# SmartChessMultiplex_SCH.net
KiCad netlist of a schematic drawn in Altium Designer
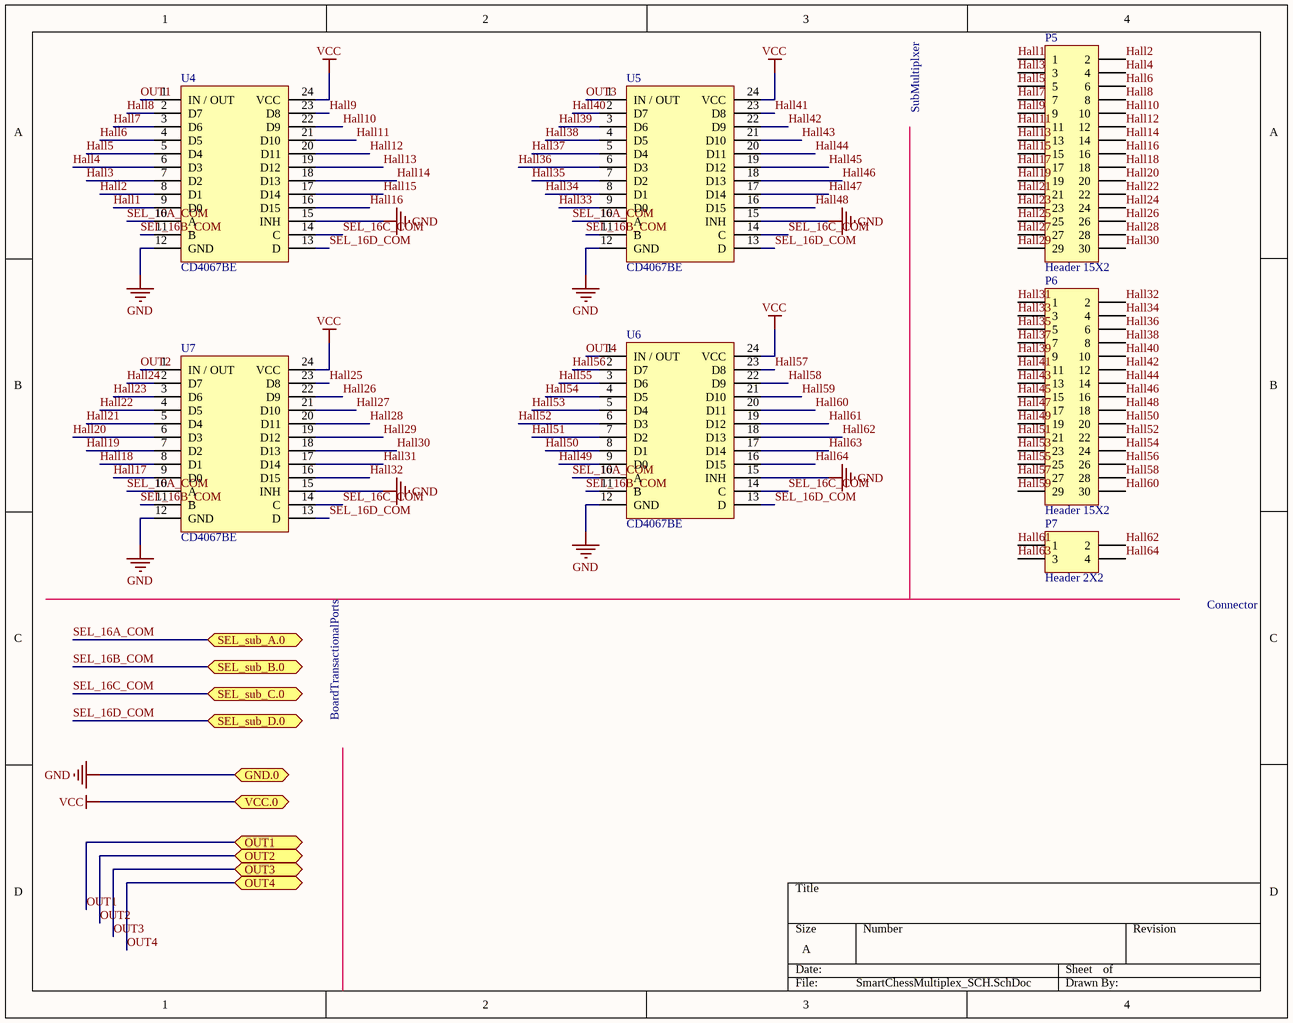
[diagram p0: SmartChessMultiplex_SCH.SchDoc]

(export (version "E")
  (design (tool "Eeschema 10.0.6"))
  (components
    (comp (ref "P5")
      (value "Header 15X2")
      (footprint "HDR2X15")
      (description "Header, 15-Pin, Dual row")
      (fields (field (name "PUBLISHER") "Altium Limited"))
      (libsource (lib "Miscellaneous Connectors") (part "Header 15X2"))
    )
    (comp (ref "P6")
      (value "Header 15X2")
      (footprint "HDR2X15")
      (description "Header, 15-Pin, Dual row")
      (fields (field (name "PUBLISHER") "Altium Limited"))
      (libsource (lib "Miscellaneous Connectors") (part "Header 15X2"))
    )
    (comp (ref "P7")
      (value "Header 2X2")
      (footprint "HDR2X2")
      (description "Header, 2-Pin, Dual row")
      (fields (field (name "PUBLISHER") "Altium Limited"))
      (libsource (lib "Miscellaneous Connectors") (part "Header 2X2"))
    )
    (comp (ref "U4") (value "CD4067BE") (footprint "DIP24") (libsource (lib "My_lib_new") (part "CD4067BE")))
    (comp (ref "U5") (value "CD4067BE") (footprint "DIP24") (libsource (lib "My_lib_new") (part "CD4067BE")))
    (comp (ref "U6") (value "CD4067BE") (footprint "DIP24") (libsource (lib "My_lib_new") (part "CD4067BE")))
    (comp (ref "U7") (value "CD4067BE") (footprint "DIP24") (libsource (lib "My_lib_new") (part "CD4067BE")))
  )
  (nets
    (net (code "1") (name "/Hall1") (class "Default")
      (node (ref "P5") (pin "1") (pinfunction "1_1") (pintype "passive"))
      (node (ref "U4") (pin "9") (pinfunction "D0_9") (pintype "passive"))
    )
    (net (code "2") (name "/Hall2") (class "Default")
      (node (ref "P5") (pin "2") (pinfunction "2_2") (pintype "passive"))
      (node (ref "U4") (pin "8") (pinfunction "D1_8") (pintype "passive"))
    )
    (net (code "3") (name "/Hall3") (class "Default")
      (node (ref "P5") (pin "3") (pinfunction "3_3") (pintype "passive"))
      (node (ref "U4") (pin "7") (pinfunction "D2_7") (pintype "passive"))
    )
    (net (code "4") (name "/Hall4") (class "Default")
      (node (ref "P5") (pin "4") (pinfunction "4_4") (pintype "passive"))
      (node (ref "U4") (pin "6") (pinfunction "D3_6") (pintype "passive"))
    )
    (net (code "5") (name "/Hall5") (class "Default")
      (node (ref "P5") (pin "5") (pinfunction "5_5") (pintype "passive"))
      (node (ref "U4") (pin "5") (pinfunction "D4_5") (pintype "passive"))
    )
    (net (code "6") (name "/Hall6") (class "Default")
      (node (ref "P5") (pin "6") (pinfunction "6_6") (pintype "passive"))
      (node (ref "U4") (pin "4") (pinfunction "D5_4") (pintype "passive"))
    )
    (net (code "7") (name "/Hall7") (class "Default")
      (node (ref "P5") (pin "7") (pinfunction "7_7") (pintype "passive"))
      (node (ref "U4") (pin "3") (pinfunction "D6_3") (pintype "passive"))
    )
    (net (code "8") (name "/Hall8") (class "Default")
      (node (ref "P5") (pin "8") (pinfunction "8_8") (pintype "passive"))
      (node (ref "U4") (pin "2") (pinfunction "D7_2") (pintype "passive"))
    )
    (net (code "9") (name "/Hall9") (class "Default")
      (node (ref "P5") (pin "9") (pinfunction "9_9") (pintype "passive"))
      (node (ref "U4") (pin "23") (pinfunction "D8_23") (pintype "passive"))
    )
    (net (code "10") (name "/Hall10") (class "Default")
      (node (ref "P5") (pin "10") (pinfunction "10_10") (pintype "passive"))
      (node (ref "U4") (pin "22") (pinfunction "D9_22") (pintype "passive"))
    )
    (net (code "11") (name "/Hall11") (class "Default")
      (node (ref "P5") (pin "11") (pinfunction "11_11") (pintype "passive"))
      (node (ref "U4") (pin "21") (pinfunction "D10_21") (pintype "passive"))
    )
    (net (code "12") (name "/Hall12") (class "Default")
      (node (ref "P5") (pin "12") (pinfunction "12_12") (pintype "passive"))
      (node (ref "U4") (pin "20") (pinfunction "D11_20") (pintype "passive"))
    )
    (net (code "13") (name "/Hall13") (class "Default")
      (node (ref "P5") (pin "13") (pinfunction "13_13") (pintype "passive"))
      (node (ref "U4") (pin "19") (pinfunction "D12_19") (pintype "passive"))
    )
    (net (code "14") (name "/Hall14") (class "Default")
      (node (ref "P5") (pin "14") (pinfunction "14_14") (pintype "passive"))
      (node (ref "U4") (pin "18") (pinfunction "D13_18") (pintype "passive"))
    )
    (net (code "15") (name "/Hall15") (class "Default")
      (node (ref "P5") (pin "15") (pinfunction "15_15") (pintype "passive"))
      (node (ref "U4") (pin "17") (pinfunction "D14_17") (pintype "passive"))
    )
    (net (code "16") (name "/Hall16") (class "Default")
      (node (ref "P5") (pin "16") (pinfunction "16_16") (pintype "passive"))
      (node (ref "U4") (pin "16") (pinfunction "D15_16") (pintype "passive"))
    )
    (net (code "17") (name "/Hall17") (class "Default")
      (node (ref "P5") (pin "17") (pinfunction "17_17") (pintype "passive"))
      (node (ref "U7") (pin "9") (pinfunction "D0_9") (pintype "passive"))
    )
    (net (code "18") (name "/Hall18") (class "Default")
      (node (ref "P5") (pin "18") (pinfunction "18_18") (pintype "passive"))
      (node (ref "U7") (pin "8") (pinfunction "D1_8") (pintype "passive"))
    )
    (net (code "19") (name "/Hall19") (class "Default")
      (node (ref "P5") (pin "19") (pinfunction "19_19") (pintype "passive"))
      (node (ref "U7") (pin "7") (pinfunction "D2_7") (pintype "passive"))
    )
    (net (code "20") (name "/Hall20") (class "Default")
      (node (ref "P5") (pin "20") (pinfunction "20_20") (pintype "passive"))
      (node (ref "U7") (pin "6") (pinfunction "D3_6") (pintype "passive"))
    )
    (net (code "21") (name "/Hall21") (class "Default")
      (node (ref "P5") (pin "21") (pinfunction "21_21") (pintype "passive"))
      (node (ref "U7") (pin "5") (pinfunction "D4_5") (pintype "passive"))
    )
    (net (code "22") (name "/Hall22") (class "Default")
      (node (ref "P5") (pin "22") (pinfunction "22_22") (pintype "passive"))
      (node (ref "U7") (pin "4") (pinfunction "D5_4") (pintype "passive"))
    )
    (net (code "23") (name "/Hall23") (class "Default")
      (node (ref "P5") (pin "23") (pinfunction "23_23") (pintype "passive"))
      (node (ref "U7") (pin "3") (pinfunction "D6_3") (pintype "passive"))
    )
    (net (code "24") (name "/Hall24") (class "Default")
      (node (ref "P5") (pin "24") (pinfunction "24_24") (pintype "passive"))
      (node (ref "U7") (pin "2") (pinfunction "D7_2") (pintype "passive"))
    )
    (net (code "25") (name "/Hall25") (class "Default")
      (node (ref "P5") (pin "25") (pinfunction "25_25") (pintype "passive"))
      (node (ref "U7") (pin "23") (pinfunction "D8_23") (pintype "passive"))
    )
    (net (code "26") (name "/Hall26") (class "Default")
      (node (ref "P5") (pin "26") (pinfunction "26_26") (pintype "passive"))
      (node (ref "U7") (pin "22") (pinfunction "D9_22") (pintype "passive"))
    )
    (net (code "27") (name "/Hall27") (class "Default")
      (node (ref "P5") (pin "27") (pinfunction "27_27") (pintype "passive"))
      (node (ref "U7") (pin "21") (pinfunction "D10_21") (pintype "passive"))
    )
    (net (code "28") (name "/Hall28") (class "Default")
      (node (ref "P5") (pin "28") (pinfunction "28_28") (pintype "passive"))
      (node (ref "U7") (pin "20") (pinfunction "D11_20") (pintype "passive"))
    )
    (net (code "29") (name "/Hall29") (class "Default")
      (node (ref "P5") (pin "29") (pinfunction "29_29") (pintype "passive"))
      (node (ref "U7") (pin "19") (pinfunction "D12_19") (pintype "passive"))
    )
    (net (code "30") (name "/Hall30") (class "Default")
      (node (ref "P5") (pin "30") (pinfunction "30_30") (pintype "passive"))
      (node (ref "U7") (pin "18") (pinfunction "D13_18") (pintype "passive"))
    )
    (net (code "31") (name "/Hall31") (class "Default")
      (node (ref "P6") (pin "1") (pinfunction "1_1") (pintype "passive"))
      (node (ref "U7") (pin "17") (pinfunction "D14_17") (pintype "passive"))
    )
    (net (code "32") (name "/Hall32") (class "Default")
      (node (ref "P6") (pin "2") (pinfunction "2_2") (pintype "passive"))
      (node (ref "U7") (pin "16") (pinfunction "D15_16") (pintype "passive"))
    )
    (net (code "33") (name "/Hall33") (class "Default")
      (node (ref "P6") (pin "3") (pinfunction "3_3") (pintype "passive"))
      (node (ref "U5") (pin "9") (pinfunction "D0_9") (pintype "passive"))
    )
    (net (code "34") (name "/Hall34") (class "Default")
      (node (ref "P6") (pin "4") (pinfunction "4_4") (pintype "passive"))
      (node (ref "U5") (pin "8") (pinfunction "D1_8") (pintype "passive"))
    )
    (net (code "35") (name "/Hall35") (class "Default")
      (node (ref "P6") (pin "5") (pinfunction "5_5") (pintype "passive"))
      (node (ref "U5") (pin "7") (pinfunction "D2_7") (pintype "passive"))
    )
    (net (code "36") (name "/Hall36") (class "Default")
      (node (ref "P6") (pin "6") (pinfunction "6_6") (pintype "passive"))
      (node (ref "U5") (pin "6") (pinfunction "D3_6") (pintype "passive"))
    )
    (net (code "37") (name "/Hall37") (class "Default")
      (node (ref "P6") (pin "7") (pinfunction "7_7") (pintype "passive"))
      (node (ref "U5") (pin "5") (pinfunction "D4_5") (pintype "passive"))
    )
    (net (code "38") (name "/Hall38") (class "Default")
      (node (ref "P6") (pin "8") (pinfunction "8_8") (pintype "passive"))
      (node (ref "U5") (pin "4") (pinfunction "D5_4") (pintype "passive"))
    )
    (net (code "39") (name "/Hall39") (class "Default")
      (node (ref "P6") (pin "9") (pinfunction "9_9") (pintype "passive"))
      (node (ref "U5") (pin "3") (pinfunction "D6_3") (pintype "passive"))
    )
    (net (code "40") (name "/Hall40") (class "Default")
      (node (ref "P6") (pin "10") (pinfunction "10_10") (pintype "passive"))
      (node (ref "U5") (pin "2") (pinfunction "D7_2") (pintype "passive"))
    )
    (net (code "41") (name "/Hall41") (class "Default")
      (node (ref "P6") (pin "11") (pinfunction "11_11") (pintype "passive"))
      (node (ref "U5") (pin "23") (pinfunction "D8_23") (pintype "passive"))
    )
    (net (code "42") (name "/Hall42") (class "Default")
      (node (ref "P6") (pin "12") (pinfunction "12_12") (pintype "passive"))
      (node (ref "U5") (pin "22") (pinfunction "D9_22") (pintype "passive"))
    )
    (net (code "43") (name "/Hall43") (class "Default")
      (node (ref "P6") (pin "13") (pinfunction "13_13") (pintype "passive"))
      (node (ref "U5") (pin "21") (pinfunction "D10_21") (pintype "passive"))
    )
    (net (code "44") (name "/Hall44") (class "Default")
      (node (ref "P6") (pin "14") (pinfunction "14_14") (pintype "passive"))
      (node (ref "U5") (pin "20") (pinfunction "D11_20") (pintype "passive"))
    )
    (net (code "45") (name "/Hall45") (class "Default")
      (node (ref "P6") (pin "15") (pinfunction "15_15") (pintype "passive"))
      (node (ref "U5") (pin "19") (pinfunction "D12_19") (pintype "passive"))
    )
    (net (code "46") (name "/Hall46") (class "Default")
      (node (ref "P6") (pin "16") (pinfunction "16_16") (pintype "passive"))
      (node (ref "U5") (pin "18") (pinfunction "D13_18") (pintype "passive"))
    )
    (net (code "47") (name "/Hall47") (class "Default")
      (node (ref "P6") (pin "17") (pinfunction "17_17") (pintype "passive"))
      (node (ref "U5") (pin "17") (pinfunction "D14_17") (pintype "passive"))
    )
    (net (code "48") (name "/Hall48") (class "Default")
      (node (ref "P6") (pin "18") (pinfunction "18_18") (pintype "passive"))
      (node (ref "U5") (pin "16") (pinfunction "D15_16") (pintype "passive"))
    )
    (net (code "49") (name "/Hall49") (class "Default")
      (node (ref "P6") (pin "19") (pinfunction "19_19") (pintype "passive"))
      (node (ref "U6") (pin "9") (pinfunction "D0_9") (pintype "passive"))
    )
    (net (code "50") (name "/Hall50") (class "Default")
      (node (ref "P6") (pin "20") (pinfunction "20_20") (pintype "passive"))
      (node (ref "U6") (pin "8") (pinfunction "D1_8") (pintype "passive"))
    )
    (net (code "51") (name "/Hall51") (class "Default")
      (node (ref "P6") (pin "21") (pinfunction "21_21") (pintype "passive"))
      (node (ref "U6") (pin "7") (pinfunction "D2_7") (pintype "passive"))
    )
    (net (code "52") (name "/Hall52") (class "Default")
      (node (ref "P6") (pin "22") (pinfunction "22_22") (pintype "passive"))
      (node (ref "U6") (pin "6") (pinfunction "D3_6") (pintype "passive"))
    )
    (net (code "53") (name "/Hall53") (class "Default")
      (node (ref "P6") (pin "23") (pinfunction "23_23") (pintype "passive"))
      (node (ref "U6") (pin "5") (pinfunction "D4_5") (pintype "passive"))
    )
    (net (code "54") (name "/Hall54") (class "Default")
      (node (ref "P6") (pin "24") (pinfunction "24_24") (pintype "passive"))
      (node (ref "U6") (pin "4") (pinfunction "D5_4") (pintype "passive"))
    )
    (net (code "55") (name "/Hall55") (class "Default")
      (node (ref "P6") (pin "25") (pinfunction "25_25") (pintype "passive"))
      (node (ref "U6") (pin "3") (pinfunction "D6_3") (pintype "passive"))
    )
    (net (code "56") (name "/Hall56") (class "Default")
      (node (ref "P6") (pin "26") (pinfunction "26_26") (pintype "passive"))
      (node (ref "U6") (pin "2") (pinfunction "D7_2") (pintype "passive"))
    )
    (net (code "57") (name "/Hall57") (class "Default")
      (node (ref "P6") (pin "27") (pinfunction "27_27") (pintype "passive"))
      (node (ref "U6") (pin "23") (pinfunction "D8_23") (pintype "passive"))
    )
    (net (code "58") (name "/Hall58") (class "Default")
      (node (ref "P6") (pin "28") (pinfunction "28_28") (pintype "passive"))
      (node (ref "U6") (pin "22") (pinfunction "D9_22") (pintype "passive"))
    )
    (net (code "59") (name "/Hall59") (class "Default")
      (node (ref "P6") (pin "29") (pinfunction "29_29") (pintype "passive"))
      (node (ref "U6") (pin "21") (pinfunction "D10_21") (pintype "passive"))
    )
    (net (code "60") (name "/Hall60") (class "Default")
      (node (ref "P6") (pin "30") (pinfunction "30_30") (pintype "passive"))
      (node (ref "U6") (pin "20") (pinfunction "D11_20") (pintype "passive"))
    )
    (net (code "61") (name "/Hall61") (class "Default")
      (node (ref "P7") (pin "1") (pinfunction "1_1") (pintype "passive"))
      (node (ref "U6") (pin "19") (pinfunction "D12_19") (pintype "passive"))
    )
    (net (code "62") (name "/Hall62") (class "Default")
      (node (ref "P7") (pin "2") (pinfunction "2_2") (pintype "passive"))
      (node (ref "U6") (pin "18") (pinfunction "D13_18") (pintype "passive"))
    )
    (net (code "63") (name "/Hall63") (class "Default")
      (node (ref "P7") (pin "3") (pinfunction "3_3") (pintype "passive"))
      (node (ref "U6") (pin "17") (pinfunction "D14_17") (pintype "passive"))
    )
    (net (code "64") (name "/Hall64") (class "Default")
      (node (ref "P7") (pin "4") (pinfunction "4_4") (pintype "passive"))
      (node (ref "U6") (pin "16") (pinfunction "D15_16") (pintype "passive"))
    )
    (net (code "65") (name "/OUT1") (class "Default")
      (node (ref "U4") (pin "1") (pinfunction "IN_/_OUT_1") (pintype "passive"))
    )
    (net (code "66") (name "/OUT2") (class "Default")
      (node (ref "U7") (pin "1") (pinfunction "IN_/_OUT_1") (pintype "passive"))
    )
    (net (code "67") (name "/OUT3") (class "Default")
      (node (ref "U5") (pin "1") (pinfunction "IN_/_OUT_1") (pintype "passive"))
    )
    (net (code "68") (name "/OUT4") (class "Default")
      (node (ref "U6") (pin "1") (pinfunction "IN_/_OUT_1") (pintype "passive"))
    )
    (net (code "69") (name "/SEL_16A_COM") (class "Default")
      (node (ref "U4") (pin "10") (pinfunction "A_10") (pintype "passive"))
      (node (ref "U5") (pin "10") (pinfunction "A_10") (pintype "passive"))
      (node (ref "U6") (pin "10") (pinfunction "A_10") (pintype "passive"))
      (node (ref "U7") (pin "10") (pinfunction "A_10") (pintype "passive"))
    )
    (net (code "70") (name "/SEL_16B_COM") (class "Default")
      (node (ref "U4") (pin "11") (pinfunction "B_11") (pintype "passive"))
      (node (ref "U5") (pin "11") (pinfunction "B_11") (pintype "passive"))
      (node (ref "U6") (pin "11") (pinfunction "B_11") (pintype "passive"))
      (node (ref "U7") (pin "11") (pinfunction "B_11") (pintype "passive"))
    )
    (net (code "71") (name "/SEL_16C_COM") (class "Default")
      (node (ref "U4") (pin "14") (pinfunction "C_14") (pintype "passive"))
      (node (ref "U5") (pin "14") (pinfunction "C_14") (pintype "passive"))
      (node (ref "U6") (pin "14") (pinfunction "C_14") (pintype "passive"))
      (node (ref "U7") (pin "14") (pinfunction "C_14") (pintype "passive"))
    )
    (net (code "72") (name "/SEL_16D_COM") (class "Default")
      (node (ref "U4") (pin "13") (pinfunction "D_13") (pintype "passive"))
      (node (ref "U5") (pin "13") (pinfunction "D_13") (pintype "passive"))
      (node (ref "U6") (pin "13") (pinfunction "D_13") (pintype "passive"))
      (node (ref "U7") (pin "13") (pinfunction "D_13") (pintype "passive"))
    )
    (net (code "73") (name "GND") (class "Default")
      (node (ref "U4") (pin "12") (pinfunction "GND_12") (pintype "passive"))
      (node (ref "U4") (pin "15") (pinfunction "INH_15") (pintype "passive"))
      (node (ref "U5") (pin "12") (pinfunction "GND_12") (pintype "passive"))
      (node (ref "U5") (pin "15") (pinfunction "INH_15") (pintype "passive"))
      (node (ref "U6") (pin "12") (pinfunction "GND_12") (pintype "passive"))
      (node (ref "U6") (pin "15") (pinfunction "INH_15") (pintype "passive"))
      (node (ref "U7") (pin "12") (pinfunction "GND_12") (pintype "passive"))
      (node (ref "U7") (pin "15") (pinfunction "INH_15") (pintype "passive"))
    )
    (net (code "74") (name "VCC") (class "Default")
      (node (ref "U4") (pin "24") (pinfunction "VCC_24") (pintype "passive"))
      (node (ref "U5") (pin "24") (pinfunction "VCC_24") (pintype "passive"))
      (node (ref "U6") (pin "24") (pinfunction "VCC_24") (pintype "passive"))
      (node (ref "U7") (pin "24") (pinfunction "VCC_24") (pintype "passive"))
    )
  )
)
